# UI-interface.net
KiCad netlist of a schematic drawn in EAGLE
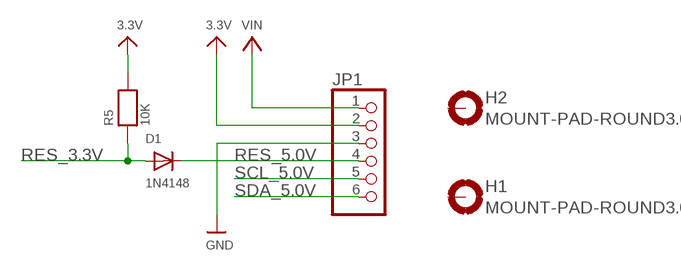
[diagram p0: schematic, sheet 1]

(export (version "E")
  (design (tool "Eeschema 10.0.6"))
  (components
    (comp (ref "D1")
      (value "1N4148")
      (footprint "eagle-import:SOD-323F")
      (libsource (lib "eagle-import") (part "DIODESOD-323F"))
    )
    (comp (ref "H1")
      (value "MOUNT-PAD-ROUND3.0")
      (footprint "eagle-import:3,0-PAD")
      (libsource (lib "eagle-import") (part "MOUNT-PAD-ROUND3.0"))
    )
    (comp (ref "H2")
      (value "MOUNT-PAD-ROUND3.0")
      (footprint "eagle-import:3,0-PAD")
      (libsource (lib "eagle-import") (part "MOUNT-PAD-ROUND3.0"))
    )
    (comp (ref "JP1")
      (value "HEADER-1X670MIL")
      (footprint "eagle-import:1X06_ROUND_70")
      (libsource (lib "eagle-import") (part "HEADER-1X670MIL"))
    )
    (comp (ref "R5")
      (value "10K")
      (footprint "eagle-import:0805")
      (libsource (lib "eagle-import") (part "RESISTOR0805"))
    )
  )
  (nets
    (net (code "1") (name "/RES_3.3V") (class "Default")
      (node (ref "D1") (pin "A") (pinfunction "A_A") (pintype "passive"))
      (node (ref "R5") (pin "1") (pinfunction "1_1") (pintype "passive"))
    )
    (net (code "2") (name "/RES_5.0V") (class "Default")
      (node (ref "D1") (pin "C") (pinfunction "C_C") (pintype "passive"))
      (node (ref "JP1") (pin "4") (pinfunction "4_4") (pintype "passive"))
    )
    (net (code "3") (name "/SCL_5.0V") (class "Default")
      (node (ref "JP1") (pin "5") (pinfunction "5_5") (pintype "passive"))
    )
    (net (code "4") (name "/SDA_5.0V") (class "Default")
      (node (ref "JP1") (pin "6") (pinfunction "6_6") (pintype "passive"))
    )
    (net (code "5") (name "3.3V") (class "Default")
      (node (ref "JP1") (pin "2") (pinfunction "2_2") (pintype "passive"))
      (node (ref "R5") (pin "2") (pinfunction "2_2") (pintype "passive"))
    )
    (net (code "6") (name "GND") (class "Default")
      (node (ref "JP1") (pin "3") (pinfunction "3_3") (pintype "passive"))
    )
    (net (code "7") (name "VIN") (class "Default")
      (node (ref "JP1") (pin "1") (pinfunction "1_1") (pintype "passive"))
    )
    (net (code "8") (name "unconnected-(H1-MOUNT-PadB3,0)") (class "Default")
      (node (ref "H1") (pin "B3,0") (pinfunction "MOUNT_B3,0") (pintype "passive"))
    )
    (net (code "9") (name "unconnected-(H2-MOUNT-PadB3,0)") (class "Default")
      (node (ref "H2") (pin "B3,0") (pinfunction "MOUNT_B3,0") (pintype "passive"))
    )
  )
)
